# 01-Power.net
KiCad netlist of a schematic drawn in Altium Designer
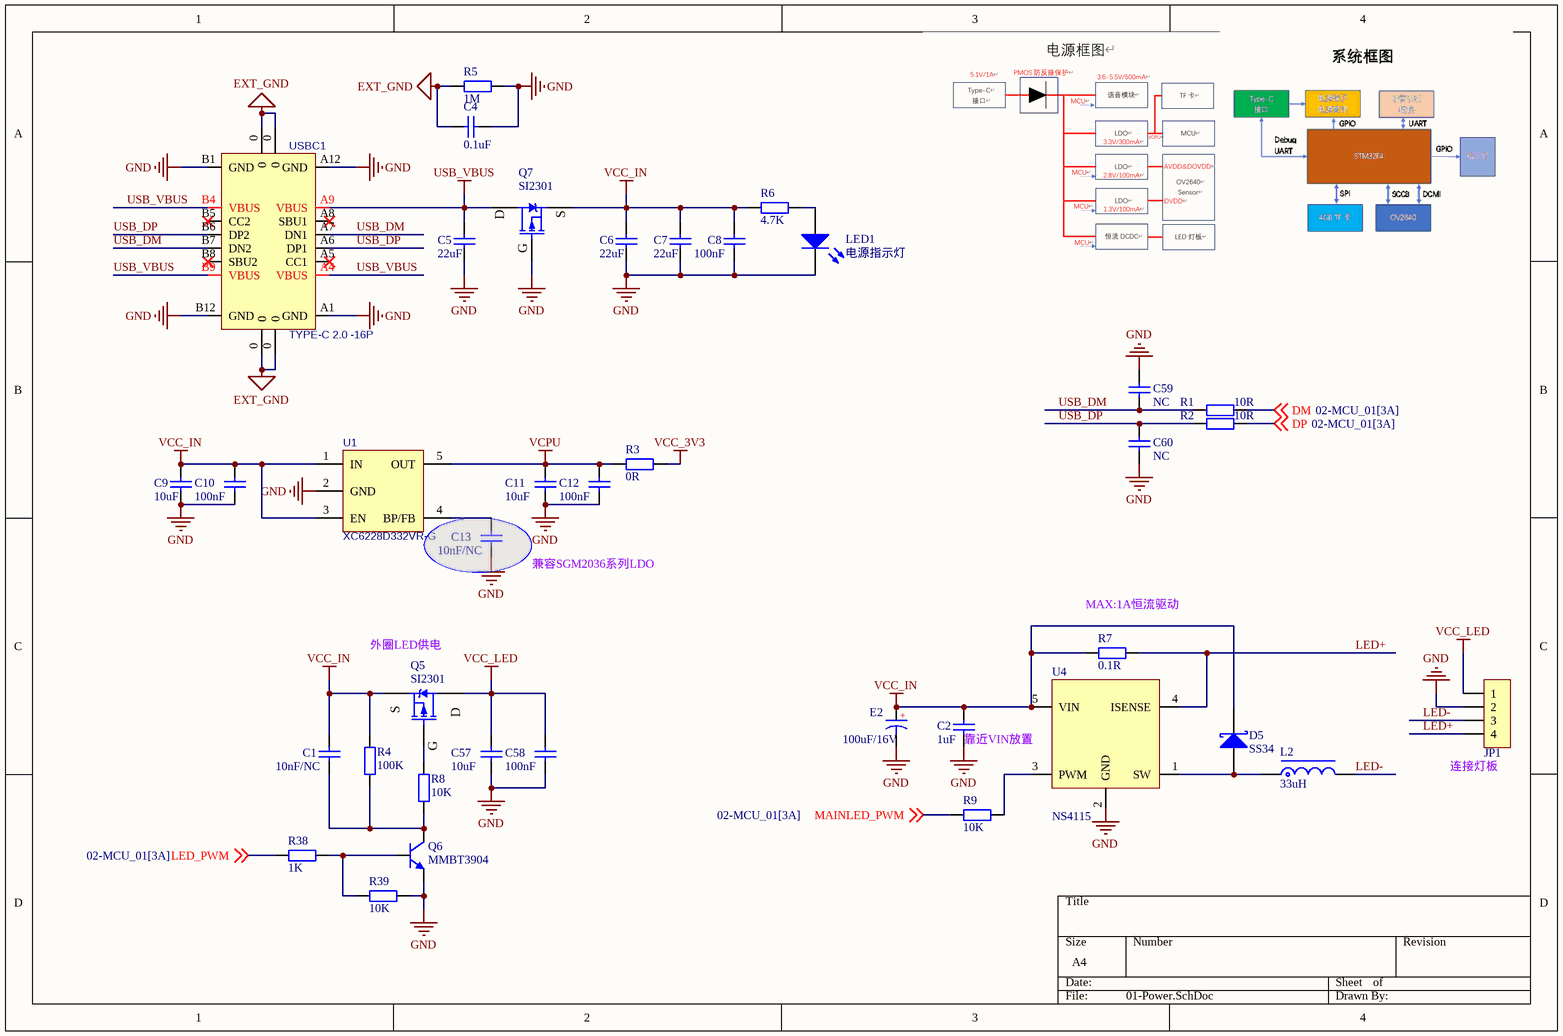
[diagram p0: 01-Power.SchDoc]

(export (version "E")
  (design (tool "Eeschema 10.0.6"))
  (components
    (comp (ref "C1")
      (value "10nF/NC")
      (footprint "C0603_M")
      (description "贴片电容/MLCC电容")
      (libsource (lib "0.1 - 电阻-电容-电感-保险丝-晶振-晶体-磁珠-电位器-法拉电容-馈通电容") (part "C"))
    )
    (comp (ref "C2")
      (value "1uF")
      (footprint "C0603_M")
      (description "贴片电容/MLCC电容")
      (libsource (lib "0.1 - 电阻-电容-电感-保险丝-晶振-晶体-磁珠-电位器-法拉电容-馈通电容") (part "C"))
    )
    (comp (ref "C4")
      (value "0.1uF")
      (footprint "C0603_M")
      (description "贴片电容/MLCC电容")
      (libsource (lib "0.1 - 电阻-电容-电感-保险丝-晶振-晶体-磁珠-电位器-法拉电容-馈通电容") (part "C"))
    )
    (comp (ref "C5")
      (value "22uF")
      (footprint "C0805_M")
      (description "贴片电容/MLCC电容")
      (libsource (lib "0.1 - 电阻-电容-电感-保险丝-晶振-晶体-磁珠-电位器-法拉电容-馈通电容") (part "C"))
    )
    (comp (ref "C6")
      (value "22uF")
      (footprint "C0805_M")
      (description "贴片电容/MLCC电容")
      (libsource (lib "0.1 - 电阻-电容-电感-保险丝-晶振-晶体-磁珠-电位器-法拉电容-馈通电容") (part "C"))
    )
    (comp (ref "C7")
      (value "22uF")
      (footprint "C0805_M")
      (description "贴片电容/MLCC电容")
      (libsource (lib "0.1 - 电阻-电容-电感-保险丝-晶振-晶体-磁珠-电位器-法拉电容-馈通电容") (part "C"))
    )
    (comp (ref "C8")
      (value "100nF")
      (footprint "C0603_M")
      (description "贴片电容/MLCC电容")
      (libsource (lib "0.1 - 电阻-电容-电感-保险丝-晶振-晶体-磁珠-电位器-法拉电容-馈通电容") (part "C"))
    )
    (comp (ref "C9")
      (value "10uF")
      (footprint "C0603_M")
      (description "贴片电容/MLCC电容")
      (libsource (lib "0.1 - 电阻-电容-电感-保险丝-晶振-晶体-磁珠-电位器-法拉电容-馈通电容") (part "C"))
    )
    (comp (ref "C10")
      (value "100nF")
      (footprint "C0603_M")
      (description "贴片电容/MLCC电容")
      (libsource (lib "0.1 - 电阻-电容-电感-保险丝-晶振-晶体-磁珠-电位器-法拉电容-馈通电容") (part "C"))
    )
    (comp (ref "C11")
      (value "10uF")
      (footprint "C0603_M")
      (description "贴片电容/MLCC电容")
      (libsource (lib "0.1 - 电阻-电容-电感-保险丝-晶振-晶体-磁珠-电位器-法拉电容-馈通电容") (part "C"))
    )
    (comp (ref "C12")
      (value "100nF")
      (footprint "C0603_M")
      (description "贴片电容/MLCC电容")
      (libsource (lib "0.1 - 电阻-电容-电感-保险丝-晶振-晶体-磁珠-电位器-法拉电容-馈通电容") (part "C"))
    )
    (comp (ref "C13")
      (value "10nF/NC")
      (footprint "C0603_M")
      (description "贴片电容/MLCC电容")
      (libsource (lib "0.1 - 电阻-电容-电感-保险丝-晶振-晶体-磁珠-电位器-法拉电容-馈通电容") (part "C"))
    )
    (comp (ref "C57")
      (value "10uF")
      (footprint "C0603_M")
      (description "贴片电容/MLCC电容")
      (libsource (lib "0.1 - 电阻-电容-电感-保险丝-晶振-晶体-磁珠-电位器-法拉电容-馈通电容") (part "C"))
    )
    (comp (ref "C58")
      (value "100nF")
      (footprint "C0603_M")
      (description "贴片电容/MLCC电容")
      (libsource (lib "0.1 - 电阻-电容-电感-保险丝-晶振-晶体-磁珠-电位器-法拉电容-馈通电容") (part "C"))
    )
    (comp (ref "C59")
      (value "NC")
      (footprint "C0402_L")
      (description "贴片电容/MLCC电容")
      (libsource (lib "0.1 - 电阻-电容-电感-保险丝-晶振-晶体-磁珠-电位器-法拉电容-馈通电容") (part "C"))
    )
    (comp (ref "C60")
      (value "NC")
      (footprint "C0402_L")
      (description "贴片电容/MLCC电容")
      (libsource (lib "0.1 - 电阻-电容-电感-保险丝-晶振-晶体-磁珠-电位器-法拉电容-馈通电容") (part "C"))
    )
    (comp (ref "D5")
      (value "SS34")
      (footprint "SMA")
      (description "肖特基二极管")
      (libsource (lib "0.2 - 二极管-TVS-ESD-整流桥-放电管") (part "SS34"))
    )
    (comp (ref "E2")
      (value "100uF/16V")
      (footprint "CS 6*6 - B")
      (description "贴片固态电容")
      (libsource (lib "0.1 - 电阻-电容-电感-保险丝-晶振-晶体-磁珠-电位器-法拉电容-馈通电容") (part "CS_SMD"))
    )
    (comp (ref "JP1")
      (value "HDR-1X4")
      (footprint "MX1.25-L-4P")
      (description "4P连接器")
      (libsource (lib "5.1 - 1.25mm连接器(FPC1.25_GH1.25_MX1.25)") (part "Header 4"))
    )
    (comp (ref "L2")
      (value "33uH")
      (footprint "CDRH74")
      (description "CDRH功率屏蔽电感")
      (libsource (lib "0.1 - 电阻-电容-电感-保险丝-晶振-晶体-磁珠-电位器-法拉电容-馈通电容") (part "L-CDRH"))
    )
    (comp (ref "LED1")
      (value "电源指示灯")
      (footprint "LED0603_G")
      (description "贴片LED")
      (libsource (lib "0.3 - LED发光二极管-IR二极管_接收管-光耦") (part "LED"))
    )
    (comp (ref "Q5")
      (value "SI2301")
      (footprint "SOT23-3N")
      (description "P沟道 20V/2.8A")
      (libsource (lib "0.4 - 三极管-场效应管-可控硅") (part "SI2301"))
    )
    (comp (ref "Q6")
      (value "MMBT3904")
      (footprint "SOT23-3N")
      (description "高频放大-NPN型")
      (libsource (lib "0.4 - 三极管-场效应管-可控硅") (part "MMBT3904"))
    )
    (comp (ref "Q7")
      (value "SI2301")
      (footprint "SOT23-3N")
      (description "P沟道 20V/2.8A")
      (libsource (lib "0.4 - 三极管-场效应管-可控硅") (part "SI2301"))
    )
    (comp (ref "R1")
      (value "10R")
      (footprint "R0402_M")
      (description "贴片电阻")
      (libsource (lib "0.1 - 电阻-电容-电感-保险丝-晶振-晶体-磁珠-电位器-法拉电容-馈通电容") (part "R"))
    )
    (comp (ref "R2")
      (value "10R")
      (footprint "R0402_M")
      (description "贴片电阻")
      (libsource (lib "0.1 - 电阻-电容-电感-保险丝-晶振-晶体-磁珠-电位器-法拉电容-馈通电容") (part "R"))
    )
    (comp (ref "R3")
      (value "0R")
      (footprint "R0603_M")
      (description "贴片电阻")
      (libsource (lib "0.1 - 电阻-电容-电感-保险丝-晶振-晶体-磁珠-电位器-法拉电容-馈通电容") (part "R"))
    )
    (comp (ref "R4")
      (value "100K")
      (footprint "R0603_M")
      (description "贴片电阻")
      (libsource (lib "0.1 - 电阻-电容-电感-保险丝-晶振-晶体-磁珠-电位器-法拉电容-馈通电容") (part "R"))
    )
    (comp (ref "R5")
      (value "1M")
      (footprint "R0603_M")
      (description "贴片电阻")
      (libsource (lib "0.1 - 电阻-电容-电感-保险丝-晶振-晶体-磁珠-电位器-法拉电容-馈通电容") (part "R"))
    )
    (comp (ref "R6")
      (value "4.7K")
      (footprint "R0402_M")
      (description "贴片电阻")
      (libsource (lib "0.1 - 电阻-电容-电感-保险丝-晶振-晶体-磁珠-电位器-法拉电容-馈通电容") (part "R"))
    )
    (comp (ref "R7")
      (value "0.1R")
      (footprint "R1206_M")
      (description "贴片电阻")
      (libsource (lib "0.1 - 电阻-电容-电感-保险丝-晶振-晶体-磁珠-电位器-法拉电容-馈通电容") (part "R"))
    )
    (comp (ref "R8")
      (value "10K")
      (footprint "R0603_M")
      (description "贴片电阻")
      (libsource (lib "0.1 - 电阻-电容-电感-保险丝-晶振-晶体-磁珠-电位器-法拉电容-馈通电容") (part "R"))
    )
    (comp (ref "R9")
      (value "10K")
      (footprint "R0603_M")
      (description "贴片电阻")
      (libsource (lib "0.1 - 电阻-电容-电感-保险丝-晶振-晶体-磁珠-电位器-法拉电容-馈通电容") (part "R"))
    )
    (comp (ref "R38")
      (value "1K")
      (footprint "R0603_M")
      (description "贴片电阻")
      (libsource (lib "0.1 - 电阻-电容-电感-保险丝-晶振-晶体-磁珠-电位器-法拉电容-馈通电容") (part "R"))
    )
    (comp (ref "R39")
      (value "10K")
      (footprint "R0603_M")
      (description "贴片电阻")
      (libsource (lib "0.1 - 电阻-电容-电感-保险丝-晶振-晶体-磁珠-电位器-法拉电容-馈通电容") (part "R"))
    )
    (comp (ref "U1")
      (value "XC6228D332VR-G")
      (footprint "SOT-23-5")
      (description "LDO 1.8V/0.3A")
      (libsource (lib "0.7 - 电源类芯片") (part "SGM2019-1.8YN5G"))
    )
    (comp (ref "U4")
      (value "NS4115")
      (footprint "SOT89-5M")
      (description "NS4115 LED恒流驱动IC，最大输出电流1A，输入支持PWM调光")
      (libsource (lib "0.7 - 电源类芯片") (part "NS4115"))
    )
    (comp (ref "USBC1")
      (value "TYPE-C 2.0 -16P")
      (footprint "USB-C-SMD_16P")
      (description "USB2.0_Type-C_16Pin母座")
      (libsource (lib "0.6 - 电源_音频_USB Type-C_HDMI_XT60_5557_D-SUB_RJ45_SD-TF_SIM插座") (part "USB2.0_Type-C_16Pin"))
    )
  )
  (nets
    (net (code "1") (name "/LED+") (class "Default")
      (node (ref "JP1") (pin "4") (pinfunction "4_4") (pintype "passive"))
      (node (ref "R7") (pin "2") (pinfunction "2_2") (pintype "passive"))
      (node (ref "U4") (pin "4") (pinfunction "ISENSE_4") (pintype "passive"))
    )
    (net (code "2") (name "/LED-") (class "Default")
      (node (ref "JP1") (pin "3") (pinfunction "3_3") (pintype "passive"))
      (node (ref "L2") (pin "2") (pinfunction "2_2") (pintype "passive"))
    )
    (net (code "3") (name "/USB_DM") (class "Default")
      (node (ref "C59") (pin "1") (pinfunction "1_1") (pintype "passive"))
      (node (ref "R1") (pin "2") (pinfunction "2_2") (pintype "passive"))
      (node (ref "USBC1") (pin "A7") (pinfunction "DN1_A7") (pintype "passive"))
      (node (ref "USBC1") (pin "B7") (pinfunction "DN2_B7") (pintype "passive"))
    )
    (net (code "4") (name "/USB_DP") (class "Default")
      (node (ref "C60") (pin "2") (pinfunction "2_2") (pintype "passive"))
      (node (ref "R2") (pin "2") (pinfunction "2_2") (pintype "passive"))
      (node (ref "USBC1") (pin "A6") (pinfunction "DP1_A6") (pintype "passive"))
      (node (ref "USBC1") (pin "B6") (pinfunction "DP2_B6") (pintype "passive"))
    )
    (net (code "5") (name "DM") (class "Default")
      (node (ref "R1") (pin "1") (pinfunction "1_1") (pintype "passive"))
    )
    (net (code "6") (name "DP") (class "Default")
      (node (ref "R2") (pin "1") (pinfunction "1_1") (pintype "passive"))
    )
    (net (code "7") (name "EXT_GND") (class "Default")
      (node (ref "C4") (pin "2") (pinfunction "2_2") (pintype "passive"))
      (node (ref "R5") (pin "2") (pinfunction "2_2") (pintype "passive"))
      (node (ref "USBC1") (pin "0") (pinfunction "0_0") (pintype "passive"))
    )
    (net (code "8") (name "GND") (class "Default")
      (node (ref "C10") (pin "1") (pinfunction "1_1") (pintype "passive"))
      (node (ref "C11") (pin "1") (pinfunction "1_1") (pintype "passive"))
      (node (ref "C12") (pin "1") (pinfunction "1_1") (pintype "passive"))
      (node (ref "C13") (pin "1") (pinfunction "1_1") (pintype "passive"))
      (node (ref "C2") (pin "1") (pinfunction "1_1") (pintype "passive"))
      (node (ref "C4") (pin "1") (pinfunction "1_1") (pintype "passive"))
      (node (ref "C5") (pin "1") (pinfunction "1_1") (pintype "passive"))
      (node (ref "C57") (pin "1") (pinfunction "1_1") (pintype "passive"))
      (node (ref "C58") (pin "1") (pinfunction "1_1") (pintype "passive"))
      (node (ref "C59") (pin "2") (pinfunction "2_2") (pintype "passive"))
      (node (ref "C6") (pin "1") (pinfunction "1_1") (pintype "passive"))
      (node (ref "C60") (pin "1") (pinfunction "1_1") (pintype "passive"))
      (node (ref "C7") (pin "1") (pinfunction "1_1") (pintype "passive"))
      (node (ref "C8") (pin "1") (pinfunction "1_1") (pintype "passive"))
      (node (ref "C9") (pin "1") (pinfunction "1_1") (pintype "passive"))
      (node (ref "E2") (pin "2") (pinfunction "2_2") (pintype "passive"))
      (node (ref "JP1") (pin "2") (pinfunction "2_2") (pintype "passive"))
      (node (ref "LED1") (pin "2") (pinfunction "K_2") (pintype "passive"))
      (node (ref "Q6") (pin "2") (pinfunction "E_2") (pintype "passive"))
      (node (ref "Q7") (pin "1") (pinfunction "G_1") (pintype "passive"))
      (node (ref "R39") (pin "1") (pinfunction "1_1") (pintype "passive"))
      (node (ref "R5") (pin "1") (pinfunction "1_1") (pintype "passive"))
      (node (ref "U1") (pin "2") (pinfunction "GND_2") (pintype "passive"))
      (node (ref "U4") (pin "2") (pinfunction "GND_2") (pintype "passive"))
      (node (ref "USBC1") (pin "A1") (pinfunction "GND_A1") (pintype "passive"))
      (node (ref "USBC1") (pin "A12") (pinfunction "GND_A12") (pintype "passive"))
      (node (ref "USBC1") (pin "B1") (pinfunction "GND_B1") (pintype "passive"))
      (node (ref "USBC1") (pin "B12") (pinfunction "GND_B12") (pintype "passive"))
    )
    (net (code "9") (name "LED_PWM") (class "Default")
      (node (ref "R38") (pin "2") (pinfunction "2_2") (pintype "passive"))
    )
    (net (code "10") (name "MAINLED_PWM") (class "Default")
      (node (ref "R9") (pin "1") (pinfunction "1_1") (pintype "passive"))
    )
    (net (code "11") (name "Net-(D5-A)") (class "Default")
      (node (ref "D5") (pin "1") (pinfunction "A_1") (pintype "passive"))
      (node (ref "L2") (pin "1") (pinfunction "1_1") (pintype "passive"))
      (node (ref "U4") (pin "1") (pinfunction "SW_1") (pintype "passive"))
    )
    (net (code "12") (name "Net-(LED1-A)") (class "Default")
      (node (ref "LED1") (pin "1") (pinfunction "A_1") (pintype "passive"))
      (node (ref "R6") (pin "1") (pinfunction "1_1") (pintype "passive"))
    )
    (net (code "13") (name "Net-(Q5-G)") (class "Default")
      (node (ref "Q5") (pin "1") (pinfunction "G_1") (pintype "passive"))
      (node (ref "R8") (pin "1") (pinfunction "1_1") (pintype "passive"))
    )
    (net (code "14") (name "Net-(Q6-B)") (class "Default")
      (node (ref "Q6") (pin "1") (pinfunction "B_1") (pintype "passive"))
      (node (ref "R38") (pin "1") (pinfunction "1_1") (pintype "passive"))
      (node (ref "R39") (pin "2") (pinfunction "2_2") (pintype "passive"))
    )
    (net (code "15") (name "Net-(Q6-C)") (class "Default")
      (node (ref "C1") (pin "1") (pinfunction "1_1") (pintype "passive"))
      (node (ref "Q6") (pin "3") (pinfunction "C_3") (pintype "passive"))
      (node (ref "R4") (pin "2") (pinfunction "2_2") (pintype "passive"))
      (node (ref "R8") (pin "2") (pinfunction "2_2") (pintype "passive"))
    )
    (net (code "16") (name "Net-(U1-BP{slash}FB)") (class "Default")
      (node (ref "C13") (pin "2") (pinfunction "2_2") (pintype "passive"))
      (node (ref "U1") (pin "4") (pinfunction "BP/FB_4") (pintype "passive"))
    )
    (net (code "17") (name "Net-(U4-PWM)") (class "Default")
      (node (ref "R9") (pin "2") (pinfunction "2_2") (pintype "passive"))
      (node (ref "U4") (pin "3") (pinfunction "PWM_3") (pintype "passive"))
    )
    (net (code "18") (name "USB_VBUS") (class "Default")
      (node (ref "C5") (pin "2") (pinfunction "2_2") (pintype "passive"))
      (node (ref "Q7") (pin "3") (pinfunction "D_3") (pintype "passive"))
      (node (ref "USBC1") (pin "A4") (pinfunction "VBUS_A4") (pintype "passive"))
      (node (ref "USBC1") (pin "A9") (pinfunction "VBUS_A9") (pintype "passive"))
      (node (ref "USBC1") (pin "B4") (pinfunction "VBUS_B4") (pintype "passive"))
      (node (ref "USBC1") (pin "B9") (pinfunction "VBUS_B9") (pintype "passive"))
    )
    (net (code "19") (name "VCC_3V3") (class "Default")
      (node (ref "R3") (pin "2") (pinfunction "2_2") (pintype "passive"))
    )
    (net (code "20") (name "VCC_IN") (class "Default")
      (node (ref "C1") (pin "2") (pinfunction "2_2") (pintype "passive"))
      (node (ref "C10") (pin "2") (pinfunction "2_2") (pintype "passive"))
      (node (ref "C2") (pin "2") (pinfunction "2_2") (pintype "passive"))
      (node (ref "C6") (pin "2") (pinfunction "2_2") (pintype "passive"))
      (node (ref "C7") (pin "2") (pinfunction "2_2") (pintype "passive"))
      (node (ref "C8") (pin "2") (pinfunction "2_2") (pintype "passive"))
      (node (ref "C9") (pin "2") (pinfunction "2_2") (pintype "passive"))
      (node (ref "D5") (pin "2") (pinfunction "K_2") (pintype "passive"))
      (node (ref "E2") (pin "1") (pinfunction "1_1") (pintype "passive"))
      (node (ref "Q5") (pin "2") (pinfunction "S_2") (pintype "passive"))
      (node (ref "Q7") (pin "2") (pinfunction "S_2") (pintype "passive"))
      (node (ref "R4") (pin "1") (pinfunction "1_1") (pintype "passive"))
      (node (ref "R6") (pin "2") (pinfunction "2_2") (pintype "passive"))
      (node (ref "R7") (pin "1") (pinfunction "1_1") (pintype "passive"))
      (node (ref "U1") (pin "1") (pinfunction "IN_1") (pintype "passive"))
      (node (ref "U1") (pin "3") (pinfunction "EN_3") (pintype "passive"))
      (node (ref "U4") (pin "5") (pinfunction "VIN_5") (pintype "passive"))
    )
    (net (code "21") (name "VCC_LED") (class "Default")
      (node (ref "C57") (pin "2") (pinfunction "2_2") (pintype "passive"))
      (node (ref "C58") (pin "2") (pinfunction "2_2") (pintype "passive"))
      (node (ref "JP1") (pin "1") (pinfunction "1_1") (pintype "passive"))
      (node (ref "Q5") (pin "3") (pinfunction "D_3") (pintype "passive"))
    )
    (net (code "22") (name "VCPU") (class "Default")
      (node (ref "C11") (pin "2") (pinfunction "2_2") (pintype "passive"))
      (node (ref "C12") (pin "2") (pinfunction "2_2") (pintype "passive"))
      (node (ref "R3") (pin "1") (pinfunction "1_1") (pintype "passive"))
      (node (ref "U1") (pin "5") (pinfunction "OUT_5") (pintype "passive"))
    )
    (net (code "23") (name "unconnected-(USBC1-CC1-PadA5)") (class "Default")
      (node (ref "USBC1") (pin "A5") (pinfunction "CC1_A5") (pintype "passive+no_connect"))
    )
    (net (code "24") (name "unconnected-(USBC1-CC2-PadB5)") (class "Default")
      (node (ref "USBC1") (pin "B5") (pinfunction "CC2_B5") (pintype "passive+no_connect"))
    )
    (net (code "25") (name "unconnected-(USBC1-SBU1-PadA8)") (class "Default")
      (node (ref "USBC1") (pin "A8") (pinfunction "SBU1_A8") (pintype "passive+no_connect"))
    )
    (net (code "26") (name "unconnected-(USBC1-SBU2-PadB8)") (class "Default")
      (node (ref "USBC1") (pin "B8") (pinfunction "SBU2_B8") (pintype "passive+no_connect"))
    )
  )
)
